# ADC_Logic.net
KiCad netlist of a schematic drawn in Altium Designer
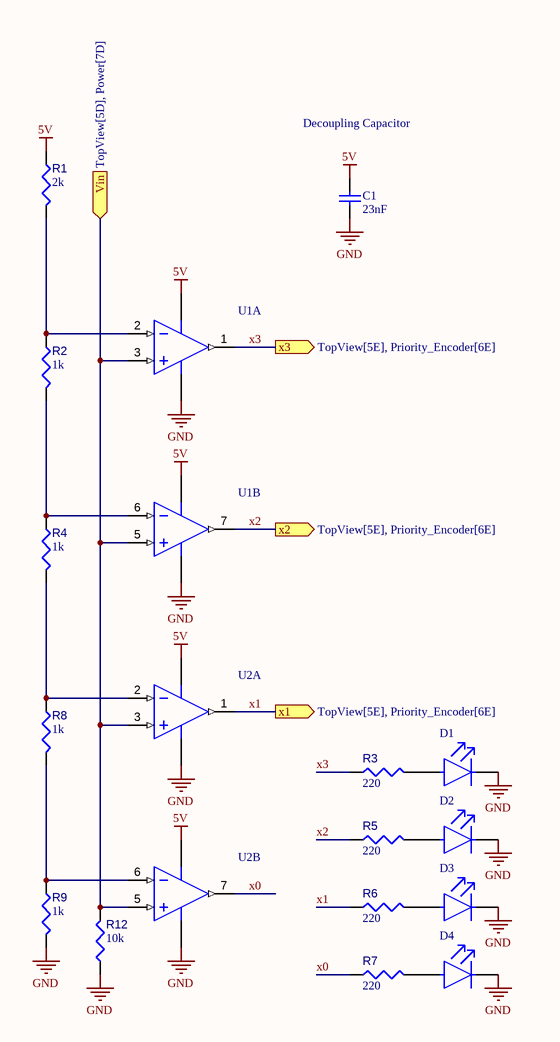
[diagram p0: ADC_Logic.SchDoc]

(export (version "E")
  (design (tool "Eeschema 10.0.6"))
  (components
    (comp (ref "C1")
      (value "23nF")
      (footprint "KEMT-C315-THT-2")
      (description "Capacitor, Ceramic, 0.01 uF, +/- 10%, 100 V, X7R, -55 to 125 degC, 2-Pin THD, RoHS, Bulk")
      (libsource (lib "Altium Content Vault") (part "CAP-NP-2"))
    )
    (comp (ref "D1")
      (value "LTL2P3KGKNN")
      (footprint "FP-LTL2P3KGKNN-MFG")
      (description "LED GREEN CLEAR T-1 3/4 T/H")
      (fields
        (field (name "MANUFACTURER") "Lite-On")
        (field (name "OCTOPART") "https://octopart.com/ltl2p3kgknn-lite-on-550036")
      )
      (libsource (lib "Altium Content Vault") (part "8706943c75ba83719d021d2fdc84c58"))
    )
    (comp (ref "D2")
      (value "LTL2P3KGKNN")
      (footprint "FP-LTL2P3KGKNN-MFG")
      (description "LED GREEN CLEAR T-1 3/4 T/H")
      (fields
        (field (name "MANUFACTURER") "Lite-On")
        (field (name "OCTOPART") "https://octopart.com/ltl2p3kgknn-lite-on-550036")
      )
      (libsource (lib "Altium Content Vault") (part "8706943c75ba83719d021d2fdc84c58"))
    )
    (comp (ref "D3")
      (value "LTL2P3KGKNN")
      (footprint "FP-LTL2P3KGKNN-MFG")
      (description "LED GREEN CLEAR T-1 3/4 T/H")
      (fields
        (field (name "MANUFACTURER") "Lite-On")
        (field (name "OCTOPART") "https://octopart.com/ltl2p3kgknn-lite-on-550036")
      )
      (libsource (lib "Altium Content Vault") (part "8706943c75ba83719d021d2fdc84c58"))
    )
    (comp (ref "D4")
      (value "LTL2P3KGKNN")
      (footprint "FP-LTL2P3KGKNN-MFG")
      (description "LED GREEN CLEAR T-1 3/4 T/H")
      (fields
        (field (name "MANUFACTURER") "Lite-On")
        (field (name "OCTOPART") "https://octopart.com/ltl2p3kgknn-lite-on-550036")
      )
      (libsource (lib "Altium Content Vault") (part "8706943c75ba83719d021d2fdc84c58"))
    )
    (comp (ref "R1")
      (value "2k")
      (footprint "RESA60-630X240")
      (description "Axial Resistor, 100 Ohm, +/- 1%, 0.25 W, -55 to 155 degC, 2-Pin THD, RoHS, Bulk")
      (fields (field (name "MANUFACTURER") "Yageo") (field (name "TOLERANCE") "1%"))
      (libsource (lib "Brandon Ramos") (part "RES-2"))
    )
    (comp (ref "R2")
      (value "1k")
      (footprint "RESA60-630X240")
      (description "Axial Resistor, 100 Ohm, +/- 1%, 0.25 W, -55 to 155 degC, 2-Pin THD, RoHS, Bulk")
      (fields (field (name "MANUFACTURER") "Yageo") (field (name "TOLERANCE") "1%"))
      (libsource (lib "Brandon Ramos") (part "RES-2"))
    )
    (comp (ref "R3")
      (value "220")
      (footprint "RESA60-630X240")
      (description "Axial Resistor, 100 Ohm, +/- 1%, 0.25 W, -55 to 155 degC, 2-Pin THD, RoHS, Bulk")
      (fields (field (name "MANUFACTURER") "Yageo") (field (name "TOLERANCE") "1%"))
      (libsource (lib "Brandon Ramos") (part "RES-2"))
    )
    (comp (ref "R4")
      (value "1k")
      (footprint "RESA60-630X240")
      (description "Axial Resistor, 100 Ohm, +/- 1%, 0.25 W, -55 to 155 degC, 2-Pin THD, RoHS, Bulk")
      (fields (field (name "MANUFACTURER") "Yageo") (field (name "TOLERANCE") "1%"))
      (libsource (lib "Brandon Ramos") (part "RES-2"))
    )
    (comp (ref "R5")
      (value "220")
      (footprint "RESA60-630X240")
      (description "Axial Resistor, 100 Ohm, +/- 1%, 0.25 W, -55 to 155 degC, 2-Pin THD, RoHS, Bulk")
      (fields (field (name "MANUFACTURER") "Yageo") (field (name "TOLERANCE") "1%"))
      (libsource (lib "Brandon Ramos") (part "RES-2"))
    )
    (comp (ref "R6")
      (value "220")
      (footprint "RESA60-630X240")
      (description "Axial Resistor, 100 Ohm, +/- 1%, 0.25 W, -55 to 155 degC, 2-Pin THD, RoHS, Bulk")
      (fields (field (name "MANUFACTURER") "Yageo") (field (name "TOLERANCE") "1%"))
      (libsource (lib "Brandon Ramos") (part "RES-2"))
    )
    (comp (ref "R7")
      (value "220")
      (footprint "RESA60-630X240")
      (description "Axial Resistor, 100 Ohm, +/- 1%, 0.25 W, -55 to 155 degC, 2-Pin THD, RoHS, Bulk")
      (fields (field (name "MANUFACTURER") "Yageo") (field (name "TOLERANCE") "1%"))
      (libsource (lib "Brandon Ramos") (part "RES-2"))
    )
    (comp (ref "R8")
      (value "1k")
      (footprint "RESA60-630X240")
      (description "Axial Resistor, 100 Ohm, +/- 1%, 0.25 W, -55 to 155 degC, 2-Pin THD, RoHS, Bulk")
      (fields (field (name "MANUFACTURER") "Yageo") (field (name "TOLERANCE") "1%"))
      (libsource (lib "Brandon Ramos") (part "RES-2"))
    )
    (comp (ref "R9")
      (value "1k")
      (footprint "RESA60-630X240")
      (description "Axial Resistor, 100 Ohm, +/- 1%, 0.25 W, -55 to 155 degC, 2-Pin THD, RoHS, Bulk")
      (fields (field (name "MANUFACTURER") "Yageo") (field (name "TOLERANCE") "1%"))
      (libsource (lib "Brandon Ramos") (part "RES-2"))
    )
    (comp (ref "R12")
      (value "10k")
      (footprint "RESA60-630X240")
      (description "Axial Resistor, 100 Ohm, +/- 1%, 0.25 W, -55 to 155 degC, 2-Pin THD, RoHS, Bulk")
      (fields (field (name "MANUFACTURER") "Yageo") (field (name "TOLERANCE") "1%"))
      (libsource (lib "Brandon Ramos") (part "RES-2"))
    )
    (comp (ref "U1")
      (value "LM358N/NOPB")
      (footprint "P0008A")
      (description "Low Power Dual Operational Amplifier, 8-pin MDIP, Pb-Free")
      (fields (field (name "MANUFACTURER") "Texas Instruments"))
      (libsource (lib "Altium Content Vault") (part "AMP-OPA-LM158-8"))
    )
    (comp (ref "U2")
      (value "LM358N/NOPB")
      (footprint "P0008A")
      (description "Low Power Dual Operational Amplifier, 8-pin MDIP, Pb-Free")
      (fields (field (name "MANUFACTURER") "Texas Instruments"))
      (libsource (lib "Altium Content Vault") (part "AMP-OPA-LM158-8"))
    )
  )
  (nets
    (net (code "1") (name "/Vin") (class "Default")
      (node (ref "R12") (pin "2") (pinfunction "2_2") (pintype "passive"))
      (node (ref "U1") (pin "3") (pinfunction "INA+_3") (pintype "input"))
      (node (ref "U1") (pin "5") (pinfunction "INB+_5") (pintype "input"))
      (node (ref "U2") (pin "3") (pinfunction "INA+_3") (pintype "input"))
      (node (ref "U2") (pin "5") (pinfunction "INB+_5") (pintype "input"))
    )
    (net (code "2") (name "/x0") (class "Default")
      (node (ref "R7") (pin "1") (pinfunction "1_1") (pintype "passive"))
      (node (ref "U2") (pin "7") (pinfunction "OUTB_7") (pintype "output"))
    )
    (net (code "3") (name "/x1") (class "Default")
      (node (ref "R6") (pin "1") (pinfunction "1_1") (pintype "passive"))
      (node (ref "U2") (pin "1") (pinfunction "OUTA_1") (pintype "output"))
    )
    (net (code "4") (name "/x2") (class "Default")
      (node (ref "R5") (pin "1") (pinfunction "1_1") (pintype "passive"))
      (node (ref "U1") (pin "7") (pinfunction "OUTB_7") (pintype "output"))
    )
    (net (code "5") (name "/x3") (class "Default")
      (node (ref "R3") (pin "1") (pinfunction "1_1") (pintype "passive"))
      (node (ref "U1") (pin "1") (pinfunction "OUTA_1") (pintype "output"))
    )
    (net (code "6") (name "5V") (class "Default")
      (node (ref "C1") (pin "2") (pinfunction "2_2") (pintype "passive"))
      (node (ref "R1") (pin "1") (pinfunction "1_1") (pintype "passive"))
      (node (ref "U1") (pin "8") (pinfunction "V+_8") (pintype "power_in"))
      (node (ref "U2") (pin "8") (pinfunction "V+_8") (pintype "power_in"))
    )
    (net (code "7") (name "GND") (class "Default")
      (node (ref "C1") (pin "1") (pinfunction "1_1") (pintype "passive"))
      (node (ref "D1") (pin "1") (pinfunction "C_1") (pintype "passive"))
      (node (ref "D2") (pin "1") (pinfunction "C_1") (pintype "passive"))
      (node (ref "D3") (pin "1") (pinfunction "C_1") (pintype "passive"))
      (node (ref "D4") (pin "1") (pinfunction "C_1") (pintype "passive"))
      (node (ref "R12") (pin "1") (pinfunction "1_1") (pintype "passive"))
      (node (ref "R9") (pin "2") (pinfunction "2_2") (pintype "passive"))
      (node (ref "U1") (pin "4") (pinfunction "GND_4") (pintype "power_in"))
      (node (ref "U2") (pin "4") (pinfunction "GND_4") (pintype "power_in"))
    )
    (net (code "8") (name "Net-(D1-A)") (class "Default")
      (node (ref "D1") (pin "2") (pinfunction "A_2") (pintype "passive"))
      (node (ref "R3") (pin "2") (pinfunction "2_2") (pintype "passive"))
    )
    (net (code "9") (name "Net-(D2-A)") (class "Default")
      (node (ref "D2") (pin "2") (pinfunction "A_2") (pintype "passive"))
      (node (ref "R5") (pin "2") (pinfunction "2_2") (pintype "passive"))
    )
    (net (code "10") (name "Net-(D3-A)") (class "Default")
      (node (ref "D3") (pin "2") (pinfunction "A_2") (pintype "passive"))
      (node (ref "R6") (pin "2") (pinfunction "2_2") (pintype "passive"))
    )
    (net (code "11") (name "Net-(D4-A)") (class "Default")
      (node (ref "D4") (pin "2") (pinfunction "A_2") (pintype "passive"))
      (node (ref "R7") (pin "2") (pinfunction "2_2") (pintype "passive"))
    )
    (net (code "12") (name "Net-(U1A-INA-)") (class "Default")
      (node (ref "R1") (pin "2") (pinfunction "2_2") (pintype "passive"))
      (node (ref "R2") (pin "1") (pinfunction "1_1") (pintype "passive"))
      (node (ref "U1") (pin "2") (pinfunction "INA-_2") (pintype "input"))
    )
    (net (code "13") (name "Net-(U1B-INB-)") (class "Default")
      (node (ref "R2") (pin "2") (pinfunction "2_2") (pintype "passive"))
      (node (ref "R4") (pin "1") (pinfunction "1_1") (pintype "passive"))
      (node (ref "U1") (pin "6") (pinfunction "INB-_6") (pintype "input"))
    )
    (net (code "14") (name "Net-(U2A-INA-)") (class "Default")
      (node (ref "R4") (pin "2") (pinfunction "2_2") (pintype "passive"))
      (node (ref "R8") (pin "1") (pinfunction "1_1") (pintype "passive"))
      (node (ref "U2") (pin "2") (pinfunction "INA-_2") (pintype "input"))
    )
    (net (code "15") (name "Net-(U2B-INB-)") (class "Default")
      (node (ref "R8") (pin "2") (pinfunction "2_2") (pintype "passive"))
      (node (ref "R9") (pin "1") (pinfunction "1_1") (pintype "passive"))
      (node (ref "U2") (pin "6") (pinfunction "INB-_6") (pintype "input"))
    )
  )
)
